# BigBed.net
KiCad netlist of a schematic drawn in Altium Designer
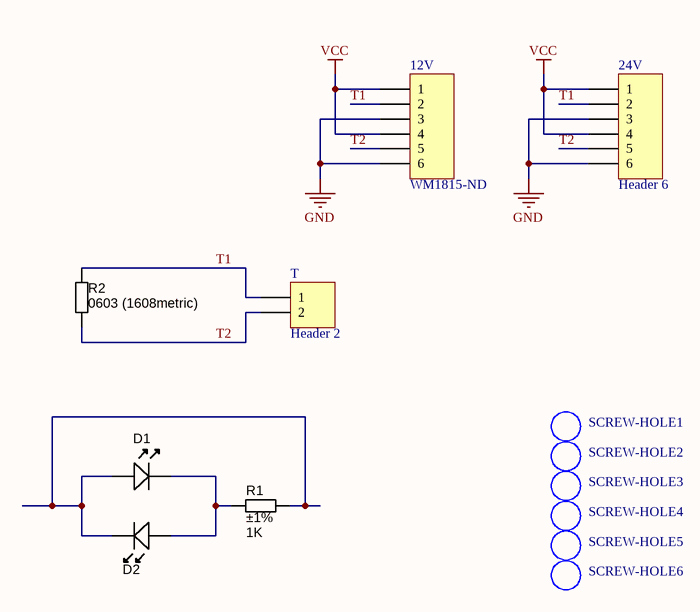
[diagram p0: BigBed.SchDoc]

(export (version "E")
  (design (tool "Eeschema 10.0.6"))
  (components
    (comp (ref "12V")
      (value "WM1815-ND")
      (footprint "Molex Micro-Fit 6")
      (description "Header, 6-Pin")
      (fields (field (name "PUBLISHER") "Altium Limited"))
      (libsource (lib "Miscellaneous Connectors") (part "Header 6"))
    )
    (comp (ref "24V")
      (value "Header 6")
      (footprint "Molex Micro-Fit 6")
      (description "Header, 6-Pin")
      (fields (field (name "PUBLISHER") "Altium Limited"))
      (libsource (lib "Miscellaneous Connectors") (part "Header 6"))
    )
    (comp (ref "D1")
      (value "~")
      (footprint "LED-0805-K")
      (description "LED 0805 SMD Red 6mcd 621nm")
      (libsource (lib "PBL - Light Sources") (part "LED_SMD_Red_0805_6mcd"))
    )
    (comp (ref "D2")
      (value "~")
      (footprint "LED-0805-K")
      (description "LED 0805 SMD Red 6mcd 621nm")
      (libsource (lib "PBL - Light Sources") (part "LED_SMD_Red_0805_6mcd"))
    )
    (comp (ref "R1")
      (value "1K")
      (footprint "RESC2012X70N")
      (description "Resistor SMD chip 1k Ohm 0.125W 1% 0805")
      (fields (field (name "TOLERANCE") "±1%") (field (name "Comment") "Thick Film"))
      (libsource (lib "PBL - Resistors") (part "RES_1K_0805_1%"))
    )
    (comp (ref "R2")
      (value "RES_EMPTY_0603")
      (footprint "RESC1608X55N")
      (description "Resistor, 08603 SMD, Empty footprint")
      (fields (field (name "PACKAGE / CASE") "0603 (1608metric)"))
      (libsource (lib "PBL - Resistors") (part "RES_EMPTY_0603"))
    )
    (comp (ref "SCREW-HOLE1")
      (value "Screw Hole")
      (footprint "M3-Hole-2")
      (libsource (lib "Schlib1") (part "Screw Hole"))
    )
    (comp (ref "SCREW-HOLE2")
      (value "Screw Hole")
      (footprint "M3-Hole-2")
      (libsource (lib "Schlib1") (part "Screw Hole"))
    )
    (comp (ref "SCREW-HOLE3")
      (value "Screw Hole")
      (footprint "M3-Hole-2")
      (libsource (lib "Schlib1") (part "Screw Hole"))
    )
    (comp (ref "SCREW-HOLE4")
      (value "Screw Hole")
      (footprint "M3-Hole-2")
      (libsource (lib "Schlib1") (part "Screw Hole"))
    )
    (comp (ref "SCREW-HOLE5")
      (value "Screw Hole")
      (footprint "M3-Hole-2")
      (libsource (lib "Schlib1") (part "Screw Hole"))
    )
    (comp (ref "SCREW-HOLE6")
      (value "Screw Hole")
      (footprint "M3-Hole-2")
      (libsource (lib "Schlib1") (part "Screw Hole"))
    )
    (comp (ref "T")
      (value "Header 2")
      (footprint "HDR1X2")
      (description "Header, 2-Pin")
      (fields (field (name "PUBLISHER") "Altium Limited"))
      (libsource (lib "Miscellaneous Connectors") (part "Header 2"))
    )
  )
  (nets
    (net (code "1") (name "/T1") (class "Default")
      (node (ref "12V") (pin "2") (pinfunction "2_2") (pintype "passive"))
      (node (ref "24V") (pin "2") (pinfunction "2_2") (pintype "passive"))
      (node (ref "R2") (pin "1") (pinfunction "1_1") (pintype "passive"))
      (node (ref "T") (pin "1") (pinfunction "1_1") (pintype "passive"))
    )
    (net (code "2") (name "/T2") (class "Default")
      (node (ref "12V") (pin "5") (pinfunction "5_5") (pintype "passive"))
      (node (ref "24V") (pin "5") (pinfunction "5_5") (pintype "passive"))
      (node (ref "R2") (pin "2") (pinfunction "2_2") (pintype "passive"))
      (node (ref "T") (pin "2") (pinfunction "2_2") (pintype "passive"))
    )
    (net (code "3") (name "GND") (class "Default")
      (node (ref "12V") (pin "3") (pinfunction "3_3") (pintype "passive"))
      (node (ref "12V") (pin "6") (pinfunction "6_6") (pintype "passive"))
      (node (ref "24V") (pin "3") (pinfunction "3_3") (pintype "passive"))
      (node (ref "24V") (pin "6") (pinfunction "6_6") (pintype "passive"))
    )
    (net (code "4") (name "Net-(D1-PadA)") (class "Default")
      (node (ref "D1") (pin "A") (pinfunction "A_A") (pintype "passive"))
      (node (ref "D2") (pin "K") (pinfunction "K_K") (pintype "passive"))
      (node (ref "R1") (pin "2") (pinfunction "2_2") (pintype "passive"))
    )
    (net (code "5") (name "Net-(D1-PadK)") (class "Default")
      (node (ref "D1") (pin "K") (pinfunction "K_K") (pintype "passive"))
      (node (ref "D2") (pin "A") (pinfunction "A_A") (pintype "passive"))
      (node (ref "R1") (pin "1") (pinfunction "1_1") (pintype "passive"))
    )
    (net (code "6") (name "VCC") (class "Default")
      (node (ref "12V") (pin "1") (pinfunction "1_1") (pintype "passive"))
      (node (ref "12V") (pin "4") (pinfunction "4_4") (pintype "passive"))
      (node (ref "24V") (pin "1") (pinfunction "1_1") (pintype "passive"))
      (node (ref "24V") (pin "4") (pinfunction "4_4") (pintype "passive"))
    )
  )
)
